# VSTIM_Power.net
KiCad netlist of a schematic drawn in Altium Designer
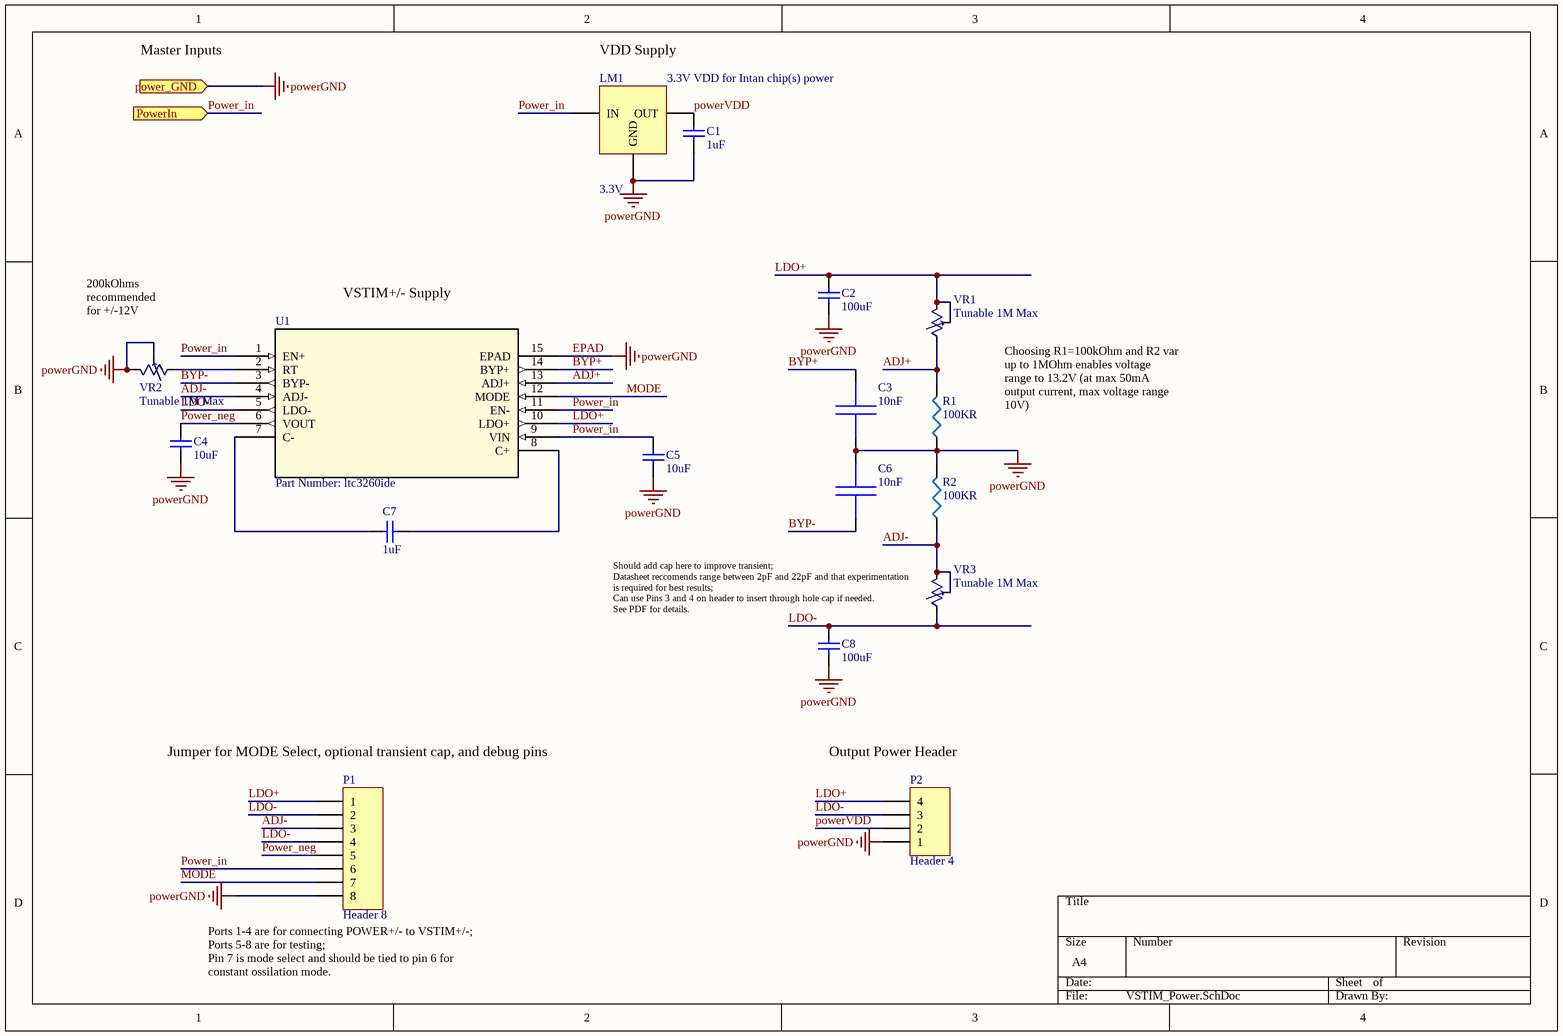
[diagram p0: VSTIM_Power.SchDoc]

(export (version "E")
  (design (tool "Eeschema 10.0.6"))
  (components
    (comp (ref "C1")
      (value "1uF")
      (footprint "standard_components:C0805")
      (description "CAP 1UF")
      (fields
        (field (name "MANUFACTURER") "TDK")
        (field (name "MANUFACTURER PART NUMBER") "C2012X5R1E105K125AA")
      )
      (libsource (lib "standard_components") (part "C2012X5R1E105K125AA"))
    )
    (comp (ref "C2")
      (value "100uF")
      (footprint "panasonic_capacitors:CAP_EEFK_D")
      (description "CAP ALUM 100UF 20% 35V SMD")
      (fields
        (field (name "MANUFACTURER") "Panasonic Electronic Components")
        (field (name "MANUFACTURER PART NUMBER") "EEE-FT1V101AP")
      )
      (libsource (lib "standard_components") (part "C2012X5R1E106K085AC"))
    )
    (comp (ref "C3")
      (value "10nF")
      (footprint "rcl_0402i_1005m_nominal")
      (description "Capacitor Non-polarized American Symbol")
      (fields
        (field (name "MANUFACTURER") "Murata Electronics North America")
        (field (name "MANUFACTURER PART NUMBER") "GRM155R71E103KA01D")
      )
      (libsource (lib "rcl_passives") (part "capacitor_npol_ame"))
    )
    (comp (ref "C4")
      (value "10uF")
      (footprint "Thesis_Testboard_V1I1:C0805")
      (description "CAP 10UF")
      (fields
        (field (name "MANUFACTURER") "Samsung Electro-Mechanics")
        (field (name "MANUFACTURER PART NUMBER") "CL21A106KAYNNNE")
      )
      (libsource (lib "standard_components") (part "C2012X5R1E106K085AC"))
    )
    (comp (ref "C5")
      (value "10uF")
      (footprint "Thesis_Testboard_V1I1:C0805")
      (description "CAP 10UF")
      (fields
        (field (name "MANUFACTURER") "Samsung Electro-Mechanics")
        (field (name "MANUFACTURER PART NUMBER") "CL21A106KAYNNNE")
      )
      (libsource (lib "standard_components") (part "C2012X5R1E106K085AC"))
    )
    (comp (ref "C6")
      (value "10nF")
      (footprint "rcl_0402i_1005m_nominal")
      (description "Capacitor Non-polarized American Symbol")
      (fields
        (field (name "MANUFACTURER") "Murata Electronics North America")
        (field (name "MANUFACTURER PART NUMBER") "GRM155R71E103KA01D")
      )
      (libsource (lib "rcl_passives") (part "capacitor_npol_ame"))
    )
    (comp (ref "C7")
      (value "1uF")
      (footprint "standard_components:C0805")
      (description "CAP 1UF")
      (fields
        (field (name "MANUFACTURER") "TDK")
        (field (name "MANUFACTURER PART NUMBER") "C2012X5R1E105K125AA")
      )
      (libsource (lib "standard_components") (part "C2012X5R1E105K125AA"))
    )
    (comp (ref "C8")
      (value "100uF")
      (footprint "panasonic_capacitors:CAP_EEFK_D")
      (description "CAP ALUM 100UF 20% 35V SMD")
      (fields
        (field (name "MANUFACTURER") "Panasonic Electronic Components")
        (field (name "MANUFACTURER PART NUMBER") "EEE-FT1V101AP")
      )
      (libsource (lib "standard_components") (part "C2012X5R1E106K085AC"))
    )
    (comp (ref "LM1")
      (value "3.3V")
      (footprint "LM1085")
      (description "LM1085ISX-3.3/NOPB")
      (fields (field (name "MANUFACTURER") "TI National Semiconductor"))
      (libsource (lib "power") (part "LM1085"))
    )
    (comp (ref "P1")
      (value "Header 8")
      (footprint "te_connectivity_headers:TE_5-535541-6")
      (description "Header, 8-Pin")
      (fields
        (field (name "MANUFACTURER") "TE Connectivity AMP Connectors")
        (field (name "MANUFACTURER PART NUMBER") "5-535541-6")
      )
      (libsource (lib "standard_components") (part "Header 8"))
    )
    (comp (ref "P2")
      (value "Header 4")
      (footprint "on_shore_rising_clamp:OSTVN04A150")
      (description "Header, 4-Pin")
      (fields
        (field (name "MANUFACTURER") "On Shore Technology Inc.")
        (field (name "MANUFACTURER PART NUMBER") "OSTVN04A150")
        (field (name "PUBLISHER") "Altium Limited")
      )
      (libsource (lib "standard_components") (part "Header 4"))
    )
    (comp (ref "R1")
      (value "100KR")
      (footprint "standard_components:R0805")
      (description "CRCW0805100KFKEA")
      (fields (field (name "MANUFACTURER") "Vishay Dale") (field (name "TOLERANCE") "1%"))
      (libsource (lib "standard_components") (part "RES100"))
    )
    (comp (ref "R2")
      (value "100KR")
      (footprint "standard_components:R0805")
      (description "CRCW0805100KFKEA")
      (fields (field (name "MANUFACTURER") "Vishay Dale") (field (name "TOLERANCE") "1%"))
      (libsource (lib "standard_components") (part "RES100"))
    )
    (comp (ref "U1")
      (value "Part Number: ltc3260ide")
      (footprint "analog_devices_power:DFN-14_DE")
      (description "IC REG CHARGE PUMP INV 14DFN")
      (fields
        (field (name "MANUFACTURER_PART_NUMBER") "ltc3260ide")
        (field (name "MANUFACTURER") "Linear Technology/Analog Devices")
        (field (name "COPYRIGHT") "Copyright (C) 2018 Accelerated Designs. All rights reserved")
      )
      (libsource (lib "analog_devices_power") (part "LTC3260IDE"))
    )
    (comp (ref "VR1")
      (value "Tunable 1M Max")
      (footprint "Thesis_Testboard_V1I1:res_var_5turn")
      (description "TRIMMER 1M OHM 0.25W J LEAD TOP")
      (fields
        (field (name "MANUFACTURER") "Nidec Copal")
        (field (name "MANUFACTURER PART NUMBER") "SM-42TW105")
      )
      (libsource (lib "standard_components") (part "RES_VAR_5TURN"))
    )
    (comp (ref "VR2")
      (value "Tunable 1M Max")
      (footprint "Thesis_Testboard_V1I1:res_var_5turn")
      (description "TRIMMER 1M OHM 0.25W J LEAD TOP")
      (fields
        (field (name "MANUFACTURER") "Nidec Copal")
        (field (name "MANUFACTURER PART NUMBER") "SM-42TW105")
      )
      (libsource (lib "standard_components") (part "RES_VAR_5TURN"))
    )
    (comp (ref "VR3")
      (value "Tunable 1M Max")
      (footprint "Thesis_Testboard_V1I1:res_var_5turn")
      (description "TRIMMER 1M OHM 0.25W J LEAD TOP")
      (fields
        (field (name "MANUFACTURER") "Nidec Copal")
        (field (name "MANUFACTURER PART NUMBER") "SM-42TW105")
      )
      (libsource (lib "standard_components") (part "RES_VAR_5TURN"))
    )
  )
  (nets
    (net (code "1") (name "/ADJ+") (class "Default")
      (node (ref "R1") (pin "2") (pinfunction "2_2") (pintype "passive"))
      (node (ref "U1") (pin "13") (pinfunction "ADJ+_13") (pintype "input"))
      (node (ref "VR1") (pin "3") (pintype "passive"))
    )
    (net (code "2") (name "/ADJ-") (class "Default")
      (node (ref "P1") (pin "3") (pinfunction "3_3") (pintype "passive"))
      (node (ref "R2") (pin "1") (pinfunction "1_1") (pintype "passive"))
      (node (ref "U1") (pin "4") (pinfunction "ADJ-_4") (pintype "input"))
      (node (ref "VR3") (pin "1") (pintype "passive"))
      (node (ref "VR3") (pin "2") (pintype "passive"))
    )
    (net (code "3") (name "/BYP+") (class "Default")
      (node (ref "C3") (pin "2") (pinfunction "2_2") (pintype "passive"))
      (node (ref "U1") (pin "14") (pinfunction "BYP+_14") (pintype "output"))
    )
    (net (code "4") (name "/BYP-") (class "Default")
      (node (ref "C6") (pin "2") (pinfunction "2_2") (pintype "passive"))
      (node (ref "U1") (pin "3") (pinfunction "BYP-_3") (pintype "output"))
    )
    (net (code "5") (name "/LDO+") (class "Default")
      (node (ref "C2") (pin "2") (pinfunction "2_2") (pintype "passive"))
      (node (ref "P1") (pin "1") (pinfunction "1_1") (pintype "passive"))
      (node (ref "P2") (pin "4") (pinfunction "4_4") (pintype "passive"))
      (node (ref "U1") (pin "10") (pinfunction "LDO+_10") (pintype "output"))
      (node (ref "VR1") (pin "1") (pintype "passive"))
      (node (ref "VR1") (pin "2") (pintype "passive"))
    )
    (net (code "6") (name "/LDO-") (class "Default")
      (node (ref "C8") (pin "2") (pinfunction "2_2") (pintype "passive"))
      (node (ref "P1") (pin "2") (pinfunction "2_2") (pintype "passive"))
      (node (ref "P1") (pin "4") (pinfunction "4_4") (pintype "passive"))
      (node (ref "P2") (pin "3") (pinfunction "3_3") (pintype "passive"))
      (node (ref "U1") (pin "5") (pinfunction "LDO-_5") (pintype "output"))
      (node (ref "VR3") (pin "3") (pintype "passive"))
    )
    (net (code "7") (name "/MODE") (class "Default")
      (node (ref "P1") (pin "7") (pinfunction "7_7") (pintype "passive"))
      (node (ref "U1") (pin "12") (pinfunction "MODE_12") (pintype "input"))
    )
    (net (code "8") (name "/Power_in") (class "Default")
      (node (ref "C5") (pin "2") (pinfunction "2_2") (pintype "passive"))
      (node (ref "LM1") (pin "3") (pinfunction "IN_3") (pintype "passive"))
      (node (ref "P1") (pin "6") (pinfunction "6_6") (pintype "passive"))
      (node (ref "U1") (pin "1") (pinfunction "EN+_1") (pintype "input"))
      (node (ref "U1") (pin "11") (pinfunction "EN-_11") (pintype "input"))
      (node (ref "U1") (pin "9") (pinfunction "VIN_9") (pintype "input"))
    )
    (net (code "9") (name "/Power_neg") (class "Default")
      (node (ref "C4") (pin "2") (pinfunction "2_2") (pintype "passive"))
      (node (ref "P1") (pin "5") (pinfunction "5_5") (pintype "passive"))
      (node (ref "U1") (pin "6") (pinfunction "VOUT_6") (pintype "output"))
    )
    (net (code "10") (name "/powerVDD") (class "Default")
      (node (ref "C1") (pin "2") (pinfunction "2_2") (pintype "passive"))
      (node (ref "LM1") (pin "2") (pinfunction "OUT_2") (pintype "passive"))
      (node (ref "P2") (pin "2") (pinfunction "2_2") (pintype "passive"))
    )
    (net (code "11") (name "Net-(U1-C+)") (class "Default")
      (node (ref "C7") (pin "1") (pinfunction "1_1") (pintype "passive"))
      (node (ref "U1") (pin "8") (pinfunction "C+_8") (pintype "passive"))
    )
    (net (code "12") (name "Net-(U1-C-)") (class "Default")
      (node (ref "C7") (pin "2") (pinfunction "2_2") (pintype "passive"))
      (node (ref "U1") (pin "7") (pinfunction "C-_7") (pintype "passive"))
    )
    (net (code "13") (name "Net-(U1-RT)") (class "Default")
      (node (ref "U1") (pin "2") (pinfunction "RT_2") (pintype "input"))
      (node (ref "VR2") (pin "3") (pintype "passive"))
    )
    (net (code "14") (name "powerGND") (class "Default")
      (node (ref "C1") (pin "1") (pinfunction "1_1") (pintype "passive"))
      (node (ref "C2") (pin "1") (pinfunction "1_1") (pintype "passive"))
      (node (ref "C3") (pin "1") (pinfunction "1_1") (pintype "passive"))
      (node (ref "C4") (pin "1") (pinfunction "1_1") (pintype "passive"))
      (node (ref "C5") (pin "1") (pinfunction "1_1") (pintype "passive"))
      (node (ref "C6") (pin "1") (pinfunction "1_1") (pintype "passive"))
      (node (ref "C8") (pin "1") (pinfunction "1_1") (pintype "passive"))
      (node (ref "LM1") (pin "1") (pinfunction "GND_1") (pintype "passive"))
      (node (ref "P1") (pin "8") (pinfunction "8_8") (pintype "passive"))
      (node (ref "P2") (pin "1") (pinfunction "1_1") (pintype "passive"))
      (node (ref "R1") (pin "1") (pinfunction "1_1") (pintype "passive"))
      (node (ref "R2") (pin "2") (pinfunction "2_2") (pintype "passive"))
      (node (ref "U1") (pin "15") (pinfunction "EPAD_15") (pintype "passive"))
      (node (ref "VR2") (pin "1") (pintype "passive"))
      (node (ref "VR2") (pin "2") (pintype "passive"))
    )
  )
)
